# boxing.net
KiCad netlist of a schematic drawn in Altium Designer
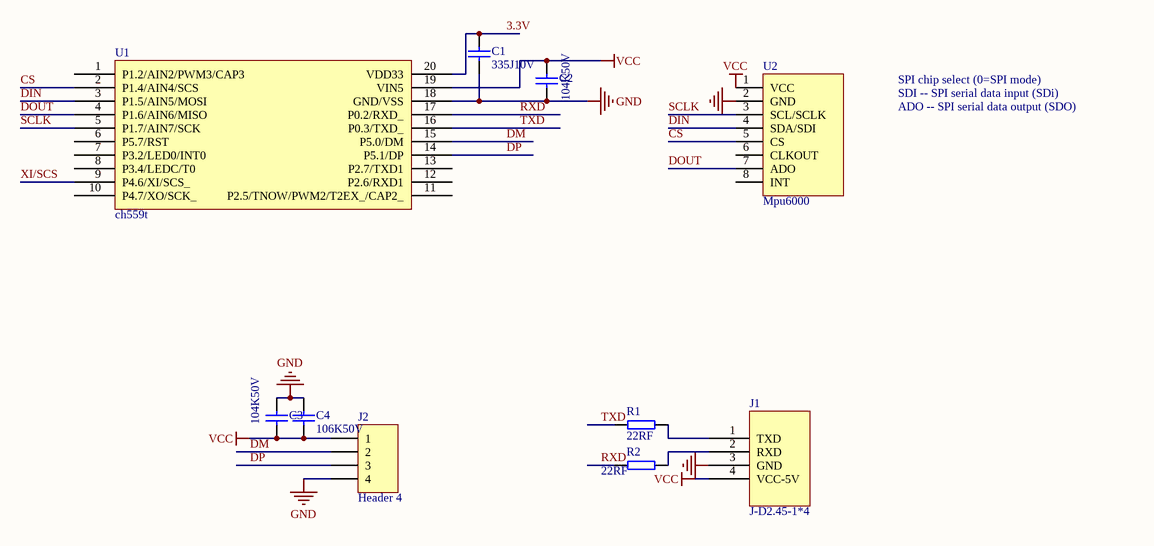
[diagram p0: boxing.SchDoc]

(export (version "E")
  (design (tool "Eeschema 10.0.6"))
  (components
    (comp (ref "C1")
      (value "335J10V")
      (footprint "C0603")
      (description "贴片电容-陶瓷")
      (libsource (lib "Capacitor") (part "C0603X7R-335J10V"))
    )
    (comp (ref "C2")
      (value "104K50V")
      (footprint "C0603")
      (description "贴片电容-陶瓷")
      (libsource (lib "Capacitor") (part "C0603X7R-104K50V"))
    )
    (comp (ref "C3")
      (value "104K50V")
      (footprint "C0603")
      (description "贴片电容-陶瓷")
      (libsource (lib "Capacitor") (part "C0603X7R-104K50V"))
    )
    (comp (ref "C4")
      (value "106K50V")
      (footprint "C0603")
      (description "贴片电容-陶瓷")
      (libsource (lib "Capacitor") (part "C0603X7R-106K50V"))
    )
    (comp (ref "J1")
      (value "J-D2.45-1*4")
      (footprint "D2.54-1*4P")
      (libsource (lib "Connector") (part "J-D2.54-1*4单排排母"))
    )
    (comp (ref "J2")
      (value "Header 4")
      (footprint "USB-AB")
      (description "Header, 4-Pin")
      (fields (field (name "PUBLISHER") "Altium Limited"))
      (libsource (lib "Miscellaneous Connectors") (part "Header 4"))
    )
    (comp (ref "R1")
      (value "22RF")
      (footprint "R0603")
      (description "贴片电阻-通用")
      (libsource (lib "Resistor") (part "R0603-22RF"))
    )
    (comp (ref "R2")
      (value "22RF")
      (footprint "R0603")
      (description "贴片电阻-通用")
      (libsource (lib "Resistor") (part "R0603-22RF"))
    )
    (comp (ref "U1")
      (value "ch559t")
      (footprint "SSOP-20")
      (description "CH559T-20pin")
      (libsource (lib "IC") (part "CH559T"))
    )
    (comp (ref "U2") (value "Mpu6000") (description "MPU6000") (libsource (lib "IC") (part "Mpu6000")))
  )
  (nets
    (net (code "1") (name "/3.3V") (class "Default")
      (node (ref "C1") (pin "1") (pinfunction "1_1") (pintype "passive"))
      (node (ref "U1") (pin "20") (pinfunction "VDD33_20") (pintype "passive"))
    )
    (net (code "2") (name "/CS") (class "Default")
      (node (ref "U1") (pin "2") (pinfunction "P1.4/AIN4/SCS_2") (pintype "passive"))
      (node (ref "U2") (pin "5") (pinfunction "CS_5") (pintype "passive"))
    )
    (net (code "3") (name "/DIN") (class "Default")
      (node (ref "U1") (pin "3") (pinfunction "P1.5/AIN5/MOSI_3") (pintype "passive"))
      (node (ref "U2") (pin "4") (pinfunction "SDA/SDI_4") (pintype "passive"))
    )
    (net (code "4") (name "/DM") (class "Default")
      (node (ref "J2") (pin "2") (pinfunction "2_2") (pintype "passive"))
      (node (ref "U1") (pin "15") (pinfunction "P5.0/DM_15") (pintype "passive"))
    )
    (net (code "5") (name "/DOUT") (class "Default")
      (node (ref "U1") (pin "4") (pinfunction "P1.6/AIN6/MISO_4") (pintype "passive"))
      (node (ref "U2") (pin "7") (pinfunction "ADO_7") (pintype "passive"))
    )
    (net (code "6") (name "/DP") (class "Default")
      (node (ref "J2") (pin "3") (pinfunction "3_3") (pintype "passive"))
      (node (ref "U1") (pin "14") (pinfunction "P5.1/DP_14") (pintype "passive"))
    )
    (net (code "7") (name "/RXD") (class "Default")
      (node (ref "R2") (pin "2") (pinfunction "2_2") (pintype "passive"))
      (node (ref "U1") (pin "17") (pinfunction "P0.2/RXD__17") (pintype "passive"))
    )
    (net (code "8") (name "/SCLK") (class "Default")
      (node (ref "U1") (pin "5") (pinfunction "P1.7/AIN7/SCK_5") (pintype "passive"))
      (node (ref "U2") (pin "3") (pinfunction "SCL/SCLK_3") (pintype "passive"))
    )
    (net (code "9") (name "/TXD") (class "Default")
      (node (ref "R1") (pin "2") (pinfunction "2_2") (pintype "passive"))
      (node (ref "U1") (pin "16") (pinfunction "P0.3/TXD__16") (pintype "passive"))
    )
    (net (code "10") (name "/XI{slash}SCS") (class "Default")
      (node (ref "U1") (pin "9") (pinfunction "P4.6/XI/SCS__9") (pintype "passive"))
    )
    (net (code "11") (name "DGND") (class "Default")
      (node (ref "J1") (pin "3") (pinfunction "GND_3") (pintype "passive"))
    )
    (net (code "12") (name "GND") (class "Default")
      (node (ref "C1") (pin "2") (pinfunction "2_2") (pintype "passive"))
      (node (ref "C2") (pin "2") (pinfunction "2_2") (pintype "passive"))
      (node (ref "C3") (pin "1") (pinfunction "1_1") (pintype "passive"))
      (node (ref "C4") (pin "2") (pinfunction "2_2") (pintype "passive"))
      (node (ref "J2") (pin "4") (pinfunction "4_4") (pintype "passive"))
      (node (ref "U1") (pin "18") (pinfunction "GND/VSS_18") (pintype "passive"))
      (node (ref "U2") (pin "2") (pinfunction "GND_2") (pintype "passive"))
    )
    (net (code "13") (name "Net-(J1-RXD)") (class "Default")
      (node (ref "J1") (pin "2") (pinfunction "RXD_2") (pintype "passive"))
      (node (ref "R2") (pin "1") (pinfunction "1_1") (pintype "passive"))
    )
    (net (code "14") (name "Net-(J1-TXD)") (class "Default")
      (node (ref "J1") (pin "1") (pinfunction "TXD_1") (pintype "passive"))
      (node (ref "R1") (pin "1") (pinfunction "1_1") (pintype "passive"))
    )
    (net (code "15") (name "VCC") (class "Default")
      (node (ref "C2") (pin "1") (pinfunction "1_1") (pintype "passive"))
      (node (ref "C3") (pin "2") (pinfunction "2_2") (pintype "passive"))
      (node (ref "C4") (pin "1") (pinfunction "1_1") (pintype "passive"))
      (node (ref "J1") (pin "4") (pinfunction "VCC-5V_4") (pintype "passive"))
      (node (ref "J2") (pin "1") (pinfunction "1_1") (pintype "passive"))
      (node (ref "U1") (pin "19") (pinfunction "VIN5_19") (pintype "passive"))
      (node (ref "U2") (pin "1") (pinfunction "VCC_1") (pintype "passive"))
    )
    (net (code "16") (name "unconnected-(U1-P1.2{slash}AIN2{slash}PWM3{slash}CAP3-Pad1)") (class "Default")
      (node (ref "U1") (pin "1") (pinfunction "P1.2/AIN2/PWM3/CAP3_1") (pintype "passive"))
    )
    (net (code "17") (name "unconnected-(U1-P2.5{slash}TNOW{slash}PWM2{slash}T2EX_{slash}CAP2_-Pad11)") (class "Default")
      (node (ref "U1") (pin "11") (pinfunction "P2.5/TNOW/PWM2/T2EX_/CAP2__11") (pintype "passive"))
    )
    (net (code "18") (name "unconnected-(U1-P2.6{slash}RXD1-Pad12)") (class "Default")
      (node (ref "U1") (pin "12") (pinfunction "P2.6/RXD1_12") (pintype "passive"))
    )
    (net (code "19") (name "unconnected-(U1-P2.7{slash}TXD1-Pad13)") (class "Default")
      (node (ref "U1") (pin "13") (pinfunction "P2.7/TXD1_13") (pintype "passive"))
    )
    (net (code "20") (name "unconnected-(U1-P3.2{slash}LED0{slash}INT0-Pad7)") (class "Default")
      (node (ref "U1") (pin "7") (pinfunction "P3.2/LED0/INT0_7") (pintype "passive"))
    )
    (net (code "21") (name "unconnected-(U1-P3.4{slash}LEDC{slash}T0-Pad8)") (class "Default")
      (node (ref "U1") (pin "8") (pinfunction "P3.4/LEDC/T0_8") (pintype "passive"))
    )
    (net (code "22") (name "unconnected-(U1-P4.7{slash}XO{slash}SCK_-Pad10)") (class "Default")
      (node (ref "U1") (pin "10") (pinfunction "P4.7/XO/SCK__10") (pintype "passive"))
    )
    (net (code "23") (name "unconnected-(U1-P5.7{slash}RST-Pad6)") (class "Default")
      (node (ref "U1") (pin "6") (pinfunction "P5.7/RST_6") (pintype "passive"))
    )
    (net (code "24") (name "unconnected-(U2-CLKOUT-Pad6)") (class "Default")
      (node (ref "U2") (pin "6") (pinfunction "CLKOUT_6") (pintype "passive"))
    )
    (net (code "25") (name "unconnected-(U2-INT-Pad8)") (class "Default")
      (node (ref "U2") (pin "8") (pinfunction "INT_8") (pintype "passive"))
    )
  )
)
